# Shematic2.net
KiCad netlist of a schematic drawn in EAGLE
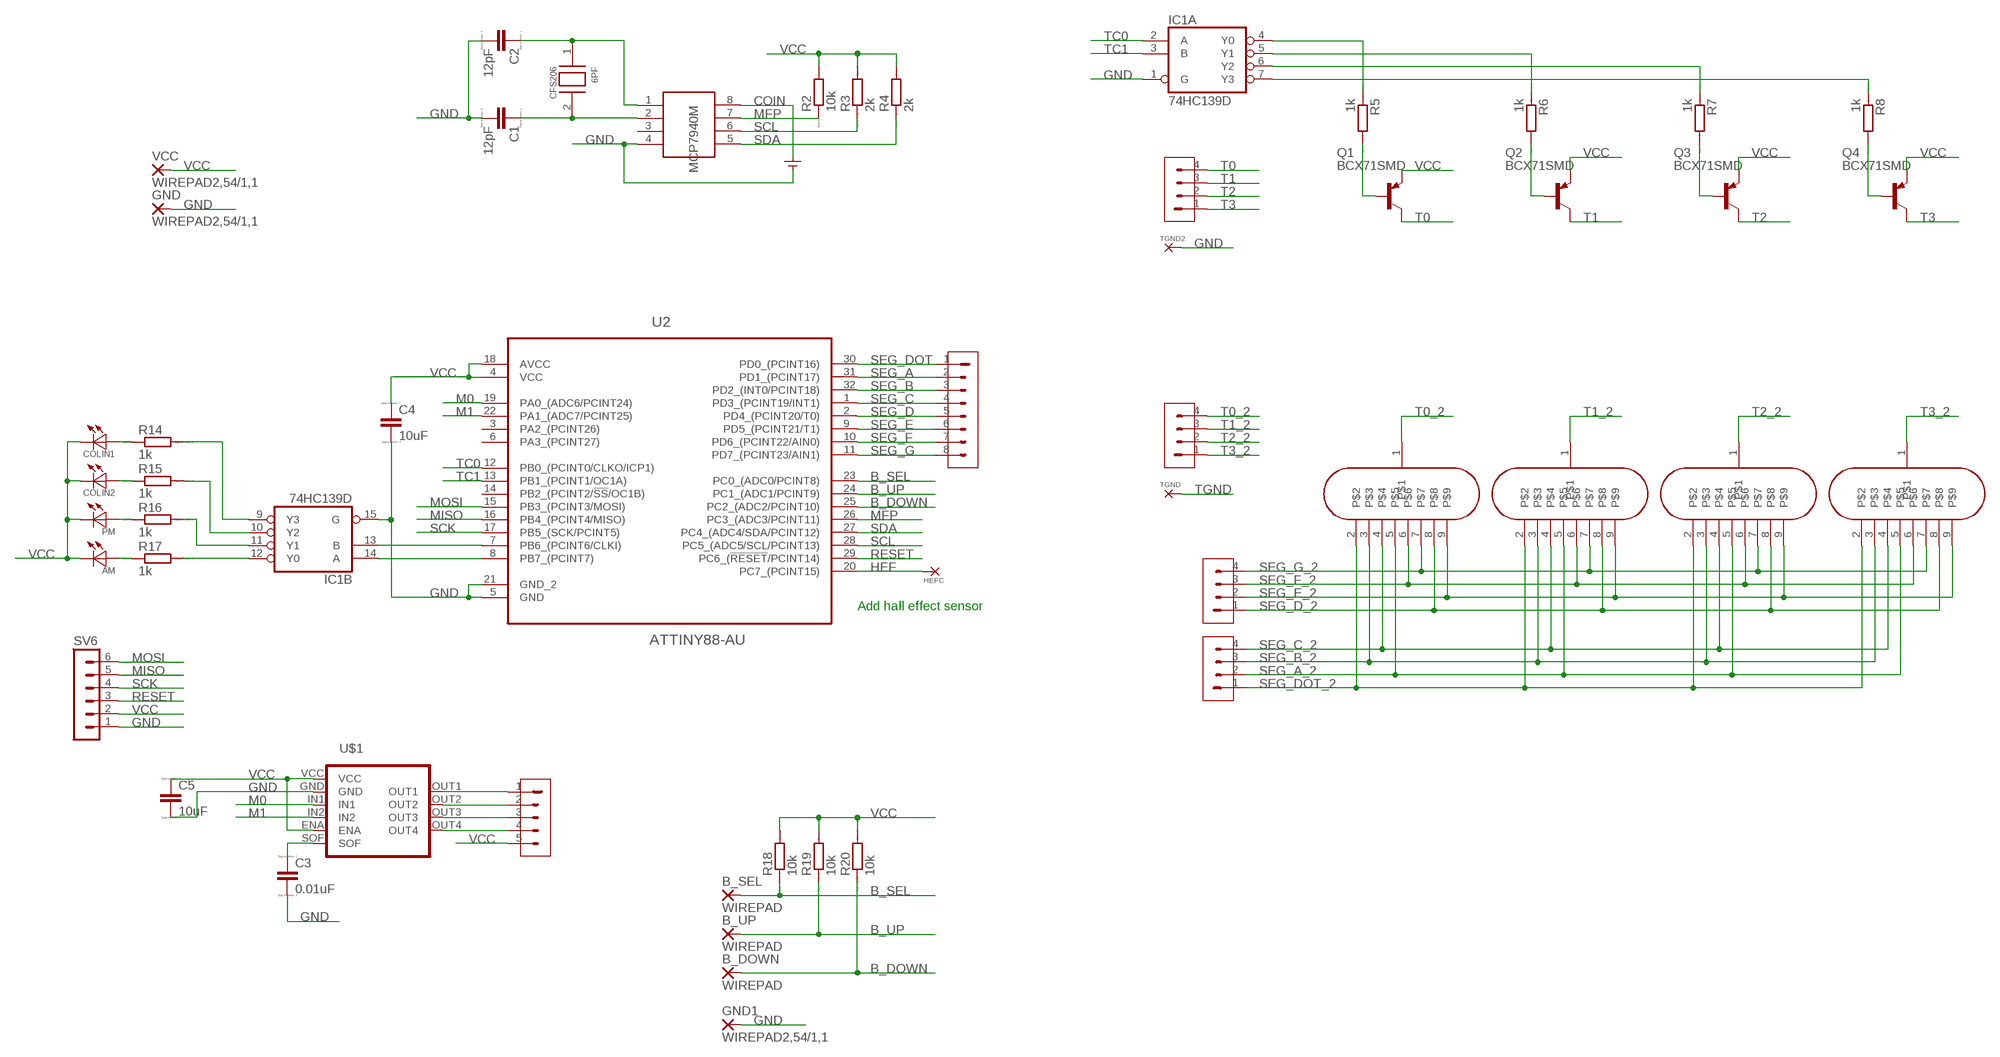
[diagram p0: schematic, sheet 1]

(export (version "E")
  (design (tool "Eeschema 10.0.6"))
  (components
    (comp (ref "6PF")
      (value "CFS206")
      (footprint "eagle-import:CFS206")
      (libsource (lib "eagle-import") (part "CFS206"))
    )
    (comp (ref "AM")
      (value "LED")
      (footprint "eagle-import:LED")
      (libsource (lib "eagle-import") (part "LED"))
    )
    (comp (ref "B_DOWN")
      (value "WIREPAD")
      (footprint "eagle-import:2,54_1,1")
      (libsource (lib "eagle-import") (part "WIREPAD2,54/1,1"))
    )
    (comp (ref "B_SEL")
      (value "WIREPAD")
      (footprint "eagle-import:2,54_1,1")
      (libsource (lib "eagle-import") (part "WIREPAD2,54/1,1"))
    )
    (comp (ref "B_UP")
      (value "WIREPAD")
      (footprint "eagle-import:2,54_1,1")
      (libsource (lib "eagle-import") (part "WIREPAD2,54/1,1"))
    )
    (comp (ref "C1")
      (value "12pF")
      (footprint "eagle-import:C1206")
      (libsource (lib "eagle-import") (part "CC1206"))
    )
    (comp (ref "C2")
      (value "12pF")
      (footprint "eagle-import:C1206")
      (libsource (lib "eagle-import") (part "CC1206"))
    )
    (comp (ref "C3")
      (value "0.01uF")
      (footprint "eagle-import:C1206")
      (libsource (lib "eagle-import") (part "CC1206"))
    )
    (comp (ref "C4")
      (value "10uF")
      (footprint "eagle-import:C1206")
      (libsource (lib "eagle-import") (part "CC1206"))
    )
    (comp (ref "C5")
      (value "10uF")
      (footprint "eagle-import:C1206")
      (libsource (lib "eagle-import") (part "CC1206"))
    )
    (comp (ref "COLIN1")
      (value "LED")
      (footprint "eagle-import:LED")
      (libsource (lib "eagle-import") (part "LED"))
    )
    (comp (ref "COLIN2")
      (value "LED")
      (footprint "eagle-import:LED")
      (libsource (lib "eagle-import") (part "LED"))
    )
    (comp (ref "GND")
      (value "WIREPAD2,54/1,1")
      (footprint "eagle-import:2,54_1,1")
      (libsource (lib "eagle-import") (part "WIREPAD2,54/1,1"))
    )
    (comp (ref "GND1")
      (value "WIREPAD2,54/1,1")
      (footprint "eagle-import:2,54_1,1")
      (libsource (lib "eagle-import") (part "WIREPAD2,54/1,1"))
    )
    (comp (ref "HEFC")
      (value "H01")
      (footprint "eagle-import:H01")
      (libsource (lib "eagle-import") (part "H01"))
    )
    (comp (ref "IC1")
      (value "74HC139D")
      (footprint "eagle-import:SO16")
      (libsource (lib "eagle-import") (part "74139DHC"))
    )
    (comp (ref "MCP7940M")
      (value "SOIC-8")
      (footprint "eagle-import:SOIC-8")
      (libsource (lib "eagle-import") (part "SOIC-8"))
    )
    (comp (ref "PM")
      (value "LED")
      (footprint "eagle-import:LED")
      (libsource (lib "eagle-import") (part "LED"))
    )
    (comp (ref "Q1")
      (value "BCX71SMD")
      (footprint "eagle-import:SOT23")
      (libsource (lib "eagle-import") (part "BCX71SMD"))
    )
    (comp (ref "Q2")
      (value "BCX71SMD")
      (footprint "eagle-import:SOT23")
      (libsource (lib "eagle-import") (part "BCX71SMD"))
    )
    (comp (ref "Q3")
      (value "BCX71SMD")
      (footprint "eagle-import:SOT23")
      (libsource (lib "eagle-import") (part "BCX71SMD"))
    )
    (comp (ref "Q4")
      (value "BCX71SMD")
      (footprint "eagle-import:SOT23")
      (libsource (lib "eagle-import") (part "BCX71SMD"))
    )
    (comp (ref "R2")
      (value "10k")
      (footprint "eagle-import:R1206")
      (libsource (lib "eagle-import") (part "RR1206"))
    )
    (comp (ref "R3")
      (value "2k")
      (footprint "eagle-import:R1206")
      (libsource (lib "eagle-import") (part "RR1206"))
    )
    (comp (ref "R4")
      (value "2k")
      (footprint "eagle-import:R1206")
      (libsource (lib "eagle-import") (part "RR1206"))
    )
    (comp (ref "R5")
      (value "1k")
      (footprint "eagle-import:R1206")
      (libsource (lib "eagle-import") (part "RR1206"))
    )
    (comp (ref "R6")
      (value "1k")
      (footprint "eagle-import:R1206")
      (libsource (lib "eagle-import") (part "RR1206"))
    )
    (comp (ref "R7")
      (value "1k")
      (footprint "eagle-import:R1206")
      (libsource (lib "eagle-import") (part "RR1206"))
    )
    (comp (ref "R8")
      (value "1k")
      (footprint "eagle-import:R1206")
      (libsource (lib "eagle-import") (part "RR1206"))
    )
    (comp (ref "R14")
      (value "1k")
      (footprint "eagle-import:R1206")
      (libsource (lib "eagle-import") (part "RR1206"))
    )
    (comp (ref "R15")
      (value "1k")
      (footprint "eagle-import:R1206")
      (libsource (lib "eagle-import") (part "RR1206"))
    )
    (comp (ref "R16")
      (value "1k")
      (footprint "eagle-import:R1206")
      (libsource (lib "eagle-import") (part "RR1206"))
    )
    (comp (ref "R17")
      (value "1k")
      (footprint "eagle-import:R1206")
      (libsource (lib "eagle-import") (part "RR1206"))
    )
    (comp (ref "R18")
      (value "10k")
      (footprint "eagle-import:R1206")
      (libsource (lib "eagle-import") (part "RR1206"))
    )
    (comp (ref "R19")
      (value "10k")
      (footprint "eagle-import:R1206")
      (libsource (lib "eagle-import") (part "RR1206"))
    )
    (comp (ref "R20")
      (value "10k")
      (footprint "eagle-import:R1206")
      (libsource (lib "eagle-import") (part "RR1206"))
    )
    (comp (ref "SV1")
      (value "H08")
      (footprint "eagle-import:H08")
      (libsource (lib "eagle-import") (part "H08"))
    )
    (comp (ref "SV2")
      (value "H04")
      (footprint "eagle-import:H04")
      (libsource (lib "eagle-import") (part "H04"))
    )
    (comp (ref "SV3")
      (value "H04")
      (footprint "eagle-import:H04")
      (libsource (lib "eagle-import") (part "H04"))
    )
    (comp (ref "SV4")
      (value "H05")
      (footprint "eagle-import:H05")
      (libsource (lib "eagle-import") (part "H05"))
    )
    (comp (ref "SV5")
      (value "H04")
      (footprint "eagle-import:H04")
      (libsource (lib "eagle-import") (part "H04"))
    )
    (comp (ref "SV6")
      (value "MA06-1")
      (footprint "eagle-import:MA06-1")
      (libsource (lib "eagle-import") (part "MA06-1"))
    )
    (comp (ref "SV7")
      (value "H04")
      (footprint "eagle-import:H04")
      (libsource (lib "eagle-import") (part "H04"))
    )
    (comp (ref "TGND")
      (value "H01")
      (footprint "eagle-import:H01")
      (libsource (lib "eagle-import") (part "H01"))
    )
    (comp (ref "TGND2")
      (value "H01")
      (footprint "eagle-import:H01")
      (libsource (lib "eagle-import") (part "H01"))
    )
    (comp (ref "TUBE0")
      (value "IV-9")
      (footprint "eagle-import:IV-9")
      (libsource (lib "eagle-import") (part "IV-9"))
    )
    (comp (ref "TUBE1")
      (value "IV-9")
      (footprint "eagle-import:IV-9")
      (libsource (lib "eagle-import") (part "IV-9"))
    )
    (comp (ref "TUBE2")
      (value "IV-9")
      (footprint "eagle-import:IV-9")
      (libsource (lib "eagle-import") (part "IV-9"))
    )
    (comp (ref "TUBE3")
      (value "IV-9")
      (footprint "eagle-import:IV-9")
      (libsource (lib "eagle-import") (part "IV-9"))
    )
    (comp (ref "U$1")
      (value "LB1848MC")
      (footprint "eagle-import:LB1848MC")
      (libsource (lib "eagle-import") (part "LB1848MC"))
    )
    (comp (ref "U$5")
      (value "COIN")
      (footprint "eagle-import:COIN")
      (libsource (lib "eagle-import") (part "COIN"))
    )
    (comp (ref "U2")
      (value "ATTINY88-AU")
      (footprint "eagle-import:QFP80P900X900X120-32N")
      (libsource (lib "eagle-import") (part "ATTINY88-AU"))
    )
    (comp (ref "VCC")
      (value "WIREPAD2,54/1,1")
      (footprint "eagle-import:2,54_1,1")
      (libsource (lib "eagle-import") (part "WIREPAD2,54/1,1"))
    )
  )
  (nets
    (net (code "1") (name "/B_DOWN") (class "Default")
      (node (ref "B_DOWN") (pin "1") (pinfunction "P_1") (pintype "passive"))
      (node (ref "R20") (pin "1") (pinfunction "1_1") (pintype "passive"))
      (node (ref "U2") (pin "25") (pinfunction "PC2_(ADC2/PCINT10)_25") (pintype "bidirectional"))
    )
    (net (code "2") (name "/B_SEL") (class "Default")
      (node (ref "B_SEL") (pin "1") (pinfunction "P_1") (pintype "passive"))
      (node (ref "R18") (pin "1") (pinfunction "1_1") (pintype "passive"))
      (node (ref "U2") (pin "23") (pinfunction "PC0_(ADC0/PCINT8)_23") (pintype "bidirectional"))
    )
    (net (code "3") (name "/B_UP") (class "Default")
      (node (ref "B_UP") (pin "1") (pinfunction "P_1") (pintype "passive"))
      (node (ref "R19") (pin "1") (pinfunction "1_1") (pintype "passive"))
      (node (ref "U2") (pin "24") (pinfunction "PC1_(ADC1/PCINT9)_24") (pintype "bidirectional"))
    )
    (net (code "4") (name "/COIN") (class "Default")
      (node (ref "MCP7940M") (pin "8") (pinfunction "P$8_8") (pintype "bidirectional"))
      (node (ref "U$5") (pin "V+") (pinfunction "V+_V+") (pintype "bidirectional"))
    )
    (net (code "5") (name "/GND") (class "Default")
      (node (ref "C1") (pin "2") (pinfunction "2_2") (pintype "passive"))
      (node (ref "C2") (pin "2") (pinfunction "2_2") (pintype "passive"))
      (node (ref "C3") (pin "2") (pinfunction "2_2") (pintype "passive"))
      (node (ref "C4") (pin "2") (pinfunction "2_2") (pintype "passive"))
      (node (ref "C5") (pin "2") (pinfunction "2_2") (pintype "passive"))
      (node (ref "GND") (pin "1") (pinfunction "P_1") (pintype "passive"))
      (node (ref "GND1") (pin "1") (pinfunction "P_1") (pintype "passive"))
      (node (ref "IC1") (pin "1") (pinfunction "G_1") (pintype "input"))
      (node (ref "IC1") (pin "15") (pinfunction "G_15") (pintype "input"))
      (node (ref "MCP7940M") (pin "4") (pinfunction "P$4_4") (pintype "bidirectional"))
      (node (ref "SV6") (pin "1") (pinfunction "1_1") (pintype "passive"))
      (node (ref "TGND2") (pin "P$1") (pinfunction "P$1_P$1") (pintype "bidirectional"))
      (node (ref "U$1") (pin "GND") (pinfunction "GND_GND") (pintype "bidirectional"))
      (node (ref "U$5") (pin "V-") (pinfunction "V-_V-") (pintype "bidirectional"))
      (node (ref "U2") (pin "21") (pinfunction "GND_2_21") (pintype "passive"))
      (node (ref "U2") (pin "5") (pinfunction "GND_5") (pintype "passive"))
    )
    (net (code "6") (name "/HEF") (class "Default")
      (node (ref "HEFC") (pin "P$1") (pinfunction "P$1_P$1") (pintype "bidirectional"))
      (node (ref "U2") (pin "20") (pinfunction "PC7_(PCINT15)_20") (pintype "bidirectional"))
    )
    (net (code "7") (name "/M0") (class "Default")
      (node (ref "U$1") (pin "IN1") (pinfunction "IN1_IN1") (pintype "bidirectional"))
      (node (ref "U2") (pin "19") (pinfunction "PA0_(ADC6/PCINT24)_19") (pintype "bidirectional"))
    )
    (net (code "8") (name "/M1") (class "Default")
      (node (ref "U$1") (pin "IN2") (pinfunction "IN2_IN2") (pintype "bidirectional"))
      (node (ref "U2") (pin "22") (pinfunction "PA1_(ADC7/PCINT25)_22") (pintype "bidirectional"))
    )
    (net (code "9") (name "/MFP") (class "Default")
      (node (ref "MCP7940M") (pin "7") (pinfunction "P$7_7") (pintype "bidirectional"))
      (node (ref "R2") (pin "1") (pinfunction "1_1") (pintype "passive"))
      (node (ref "U2") (pin "26") (pinfunction "PC3_(ADC3/PCINT11)_26") (pintype "bidirectional"))
    )
    (net (code "10") (name "/MISO") (class "Default")
      (node (ref "SV6") (pin "5") (pinfunction "5_5") (pintype "passive"))
      (node (ref "U2") (pin "16") (pinfunction "PB4_(PCINT4/MISO)_16") (pintype "bidirectional"))
    )
    (net (code "11") (name "/MOSI") (class "Default")
      (node (ref "SV6") (pin "6") (pinfunction "6_6") (pintype "passive"))
      (node (ref "U2") (pin "15") (pinfunction "PB3_(PCINT3/MOSI)_15") (pintype "bidirectional"))
    )
    (net (code "12") (name "/RESET") (class "Default")
      (node (ref "SV6") (pin "3") (pinfunction "3_3") (pintype "passive"))
      (node (ref "U2") (pin "29") (pinfunction "PC6_(~{RESET}/PCINT14)_29") (pintype "bidirectional"))
    )
    (net (code "13") (name "/SCK") (class "Default")
      (node (ref "SV6") (pin "4") (pinfunction "4_4") (pintype "passive"))
      (node (ref "U2") (pin "17") (pinfunction "PB5_(SCK/PCINT5)_17") (pintype "bidirectional"))
    )
    (net (code "14") (name "/SCL") (class "Default")
      (node (ref "MCP7940M") (pin "6") (pinfunction "P$6_6") (pintype "bidirectional"))
      (node (ref "R3") (pin "1") (pinfunction "1_1") (pintype "passive"))
      (node (ref "U2") (pin "28") (pinfunction "PC5_(ADC5/SCL/PCINT13)_28") (pintype "bidirectional"))
    )
    (net (code "15") (name "/SDA") (class "Default")
      (node (ref "MCP7940M") (pin "5") (pinfunction "P$5_5") (pintype "bidirectional"))
      (node (ref "R4") (pin "1") (pinfunction "1_1") (pintype "passive"))
      (node (ref "U2") (pin "27") (pinfunction "PC4_(ADC4/SDA/PCINT12)_27") (pintype "bidirectional"))
    )
    (net (code "16") (name "/SEG_A") (class "Default")
      (node (ref "SV1") (pin "2") (pinfunction "2_2") (pintype "bidirectional"))
      (node (ref "U2") (pin "31") (pinfunction "PD1_(PCINT17)_31") (pintype "bidirectional"))
    )
    (net (code "17") (name "/SEG_A_2") (class "Default")
      (node (ref "SV7") (pin "2") (pinfunction "2_2") (pintype "bidirectional"))
      (node (ref "TUBE0") (pin "5") (pinfunction "P$5_5") (pintype "bidirectional"))
      (node (ref "TUBE1") (pin "5") (pinfunction "P$5_5") (pintype "bidirectional"))
      (node (ref "TUBE2") (pin "5") (pinfunction "P$5_5") (pintype "bidirectional"))
      (node (ref "TUBE3") (pin "5") (pinfunction "P$5_5") (pintype "bidirectional"))
    )
    (net (code "18") (name "/SEG_B") (class "Default")
      (node (ref "SV1") (pin "3") (pinfunction "3_3") (pintype "bidirectional"))
      (node (ref "U2") (pin "32") (pinfunction "PD2_(INT0/PCINT18)_32") (pintype "bidirectional"))
    )
    (net (code "19") (name "/SEG_B_2") (class "Default")
      (node (ref "SV7") (pin "3") (pinfunction "3_3") (pintype "bidirectional"))
      (node (ref "TUBE0") (pin "3") (pinfunction "P$3_3") (pintype "bidirectional"))
      (node (ref "TUBE1") (pin "3") (pinfunction "P$3_3") (pintype "bidirectional"))
      (node (ref "TUBE2") (pin "3") (pinfunction "P$3_3") (pintype "bidirectional"))
      (node (ref "TUBE3") (pin "3") (pinfunction "P$3_3") (pintype "bidirectional"))
    )
    (net (code "20") (name "/SEG_C") (class "Default")
      (node (ref "SV1") (pin "4") (pinfunction "4_4") (pintype "bidirectional"))
      (node (ref "U2") (pin "1") (pinfunction "PD3_(PCINT19/INT1)_1") (pintype "bidirectional"))
    )
    (net (code "21") (name "/SEG_C_2") (class "Default")
      (node (ref "SV7") (pin "4") (pinfunction "4_4") (pintype "bidirectional"))
      (node (ref "TUBE0") (pin "4") (pinfunction "P$4_4") (pintype "bidirectional"))
      (node (ref "TUBE1") (pin "4") (pinfunction "P$4_4") (pintype "bidirectional"))
      (node (ref "TUBE2") (pin "4") (pinfunction "P$4_4") (pintype "bidirectional"))
      (node (ref "TUBE3") (pin "4") (pinfunction "P$4_4") (pintype "bidirectional"))
    )
    (net (code "22") (name "/SEG_D") (class "Default")
      (node (ref "SV1") (pin "5") (pinfunction "5_5") (pintype "bidirectional"))
      (node (ref "U2") (pin "2") (pinfunction "PD4_(PCINT20/T0)_2") (pintype "bidirectional"))
    )
    (net (code "23") (name "/SEG_DOT") (class "Default")
      (node (ref "SV1") (pin "1") (pinfunction "1_1") (pintype "bidirectional"))
      (node (ref "U2") (pin "30") (pinfunction "PD0_(PCINT16)_30") (pintype "bidirectional"))
    )
    (net (code "24") (name "/SEG_DOT_2") (class "Default")
      (node (ref "SV7") (pin "1") (pinfunction "1_1") (pintype "bidirectional"))
      (node (ref "TUBE0") (pin "2") (pinfunction "P$2_2") (pintype "bidirectional"))
      (node (ref "TUBE1") (pin "2") (pinfunction "P$2_2") (pintype "bidirectional"))
      (node (ref "TUBE2") (pin "2") (pinfunction "P$2_2") (pintype "bidirectional"))
      (node (ref "TUBE3") (pin "2") (pinfunction "P$2_2") (pintype "bidirectional"))
    )
    (net (code "25") (name "/SEG_D_2") (class "Default")
      (node (ref "SV2") (pin "1") (pinfunction "1_1") (pintype "bidirectional"))
      (node (ref "TUBE0") (pin "8") (pinfunction "P$8_8") (pintype "bidirectional"))
      (node (ref "TUBE1") (pin "8") (pinfunction "P$8_8") (pintype "bidirectional"))
      (node (ref "TUBE2") (pin "8") (pinfunction "P$8_8") (pintype "bidirectional"))
      (node (ref "TUBE3") (pin "8") (pinfunction "P$8_8") (pintype "bidirectional"))
    )
    (net (code "26") (name "/SEG_E") (class "Default")
      (node (ref "SV1") (pin "6") (pinfunction "6_6") (pintype "bidirectional"))
      (node (ref "U2") (pin "9") (pinfunction "PD5_(PCINT21/T1)_9") (pintype "bidirectional"))
    )
    (net (code "27") (name "/SEG_E_2") (class "Default")
      (node (ref "SV2") (pin "2") (pinfunction "2_2") (pintype "bidirectional"))
      (node (ref "TUBE0") (pin "9") (pinfunction "P$9_9") (pintype "bidirectional"))
      (node (ref "TUBE1") (pin "9") (pinfunction "P$9_9") (pintype "bidirectional"))
      (node (ref "TUBE2") (pin "9") (pinfunction "P$9_9") (pintype "bidirectional"))
      (node (ref "TUBE3") (pin "9") (pinfunction "P$9_9") (pintype "bidirectional"))
    )
    (net (code "28") (name "/SEG_F") (class "Default")
      (node (ref "SV1") (pin "7") (pinfunction "7_7") (pintype "bidirectional"))
      (node (ref "U2") (pin "10") (pinfunction "PD6_(PCINT22/AIN0)_10") (pintype "bidirectional"))
    )
    (net (code "29") (name "/SEG_F_2") (class "Default")
      (node (ref "SV2") (pin "3") (pinfunction "3_3") (pintype "bidirectional"))
      (node (ref "TUBE0") (pin "6") (pinfunction "P$6_6") (pintype "bidirectional"))
      (node (ref "TUBE1") (pin "6") (pinfunction "P$6_6") (pintype "bidirectional"))
      (node (ref "TUBE2") (pin "6") (pinfunction "P$6_6") (pintype "bidirectional"))
      (node (ref "TUBE3") (pin "6") (pinfunction "P$6_6") (pintype "bidirectional"))
    )
    (net (code "30") (name "/SEG_G") (class "Default")
      (node (ref "SV1") (pin "8") (pinfunction "8_8") (pintype "bidirectional"))
      (node (ref "U2") (pin "11") (pinfunction "PD7_(PCINT23/AIN1)_11") (pintype "bidirectional"))
    )
    (net (code "31") (name "/SEG_G_2") (class "Default")
      (node (ref "SV2") (pin "4") (pinfunction "4_4") (pintype "bidirectional"))
      (node (ref "TUBE0") (pin "7") (pinfunction "P$7_7") (pintype "bidirectional"))
      (node (ref "TUBE1") (pin "7") (pinfunction "P$7_7") (pintype "bidirectional"))
      (node (ref "TUBE2") (pin "7") (pinfunction "P$7_7") (pintype "bidirectional"))
      (node (ref "TUBE3") (pin "7") (pinfunction "P$7_7") (pintype "bidirectional"))
    )
    (net (code "32") (name "/T0") (class "Default")
      (node (ref "Q1") (pin "3") (pinfunction "C_3") (pintype "passive"))
      (node (ref "SV5") (pin "4") (pinfunction "4_4") (pintype "bidirectional"))
    )
    (net (code "33") (name "/T0_2") (class "Default")
      (node (ref "SV3") (pin "4") (pinfunction "4_4") (pintype "bidirectional"))
      (node (ref "TUBE0") (pin "1") (pinfunction "P$1_1") (pintype "bidirectional"))
    )
    (net (code "34") (name "/T1") (class "Default")
      (node (ref "Q2") (pin "3") (pinfunction "C_3") (pintype "passive"))
      (node (ref "SV5") (pin "3") (pinfunction "3_3") (pintype "bidirectional"))
    )
    (net (code "35") (name "/T1_2") (class "Default")
      (node (ref "SV3") (pin "3") (pinfunction "3_3") (pintype "bidirectional"))
      (node (ref "TUBE1") (pin "1") (pinfunction "P$1_1") (pintype "bidirectional"))
    )
    (net (code "36") (name "/T2") (class "Default")
      (node (ref "Q3") (pin "3") (pinfunction "C_3") (pintype "passive"))
      (node (ref "SV5") (pin "2") (pinfunction "2_2") (pintype "bidirectional"))
    )
    (net (code "37") (name "/T2_2") (class "Default")
      (node (ref "SV3") (pin "2") (pinfunction "2_2") (pintype "bidirectional"))
      (node (ref "TUBE2") (pin "1") (pinfunction "P$1_1") (pintype "bidirectional"))
    )
    (net (code "38") (name "/T3") (class "Default")
      (node (ref "Q4") (pin "3") (pinfunction "C_3") (pintype "passive"))
      (node (ref "SV5") (pin "1") (pinfunction "1_1") (pintype "bidirectional"))
    )
    (net (code "39") (name "/T3_2") (class "Default")
      (node (ref "SV3") (pin "1") (pinfunction "1_1") (pintype "bidirectional"))
      (node (ref "TUBE3") (pin "1") (pinfunction "P$1_1") (pintype "bidirectional"))
    )
    (net (code "40") (name "/TC0") (class "Default")
      (node (ref "IC1") (pin "2") (pinfunction "A_2") (pintype "input"))
      (node (ref "U2") (pin "12") (pinfunction "PB0_(PCINT0/CLKO/ICP1)_12") (pintype "bidirectional"))
    )
    (net (code "41") (name "/TC1") (class "Default")
      (node (ref "IC1") (pin "3") (pinfunction "B_3") (pintype "input"))
      (node (ref "U2") (pin "13") (pinfunction "PB1_(PCINT1/OC1A)_13") (pintype "bidirectional"))
    )
    (net (code "42") (name "/TGND") (class "Default")
      (node (ref "TGND") (pin "P$1") (pinfunction "P$1_P$1") (pintype "bidirectional"))
    )
    (net (code "43") (name "/VCC") (class "Default")
      (node (ref "AM") (pin "P$2") (pinfunction "P$2_P$2") (pintype "bidirectional"))
      (node (ref "C4") (pin "1") (pinfunction "1_1") (pintype "passive"))
      (node (ref "C5") (pin "1") (pinfunction "1_1") (pintype "passive"))
      (node (ref "COLIN1") (pin "P$2") (pinfunction "P$2_P$2") (pintype "bidirectional"))
      (node (ref "COLIN2") (pin "P$2") (pinfunction "P$2_P$2") (pintype "bidirectional"))
      (node (ref "PM") (pin "P$2") (pinfunction "P$2_P$2") (pintype "bidirectional"))
      (node (ref "Q1") (pin "2") (pinfunction "E_2") (pintype "passive"))
      (node (ref "Q2") (pin "2") (pinfunction "E_2") (pintype "passive"))
      (node (ref "Q3") (pin "2") (pinfunction "E_2") (pintype "passive"))
      (node (ref "Q4") (pin "2") (pinfunction "E_2") (pintype "passive"))
      (node (ref "R18") (pin "2") (pinfunction "2_2") (pintype "passive"))
      (node (ref "R19") (pin "2") (pinfunction "2_2") (pintype "passive"))
      (node (ref "R2") (pin "2") (pinfunction "2_2") (pintype "passive"))
      (node (ref "R20") (pin "2") (pinfunction "2_2") (pintype "passive"))
      (node (ref "R3") (pin "2") (pinfunction "2_2") (pintype "passive"))
      (node (ref "R4") (pin "2") (pinfunction "2_2") (pintype "passive"))
      (node (ref "SV4") (pin "5") (pinfunction "5_5") (pintype "bidirectional"))
      (node (ref "SV6") (pin "2") (pinfunction "2_2") (pintype "passive"))
      (node (ref "U$1") (pin "ENA") (pinfunction "ENA_ENA") (pintype "bidirectional"))
      (node (ref "U$1") (pin "VCC") (pinfunction "VCC_VCC") (pintype "bidirectional"))
      (node (ref "U2") (pin "18") (pinfunction "AVCC_18") (pintype "power_in"))
      (node (ref "U2") (pin "4") (pinfunction "VCC_4") (pintype "power_in"))
      (node (ref "VCC") (pin "1") (pinfunction "P_1") (pintype "passive"))
    )
    (net (code "44") (name "Net-(6PF-P$1)") (class "Default")
      (node (ref "6PF") (pin "1") (pinfunction "P$1_1") (pintype "bidirectional"))
      (node (ref "C2") (pin "1") (pinfunction "1_1") (pintype "passive"))
      (node (ref "MCP7940M") (pin "1") (pinfunction "P$1_1") (pintype "bidirectional"))
    )
    (net (code "45") (name "Net-(6PF-P$2)") (class "Default")
      (node (ref "6PF") (pin "2") (pinfunction "P$2_2") (pintype "bidirectional"))
      (node (ref "C1") (pin "1") (pinfunction "1_1") (pintype "passive"))
      (node (ref "MCP7940M") (pin "2") (pinfunction "P$2_2") (pintype "bidirectional"))
    )
    (net (code "46") (name "Net-(AM-PadP$1)") (class "Default")
      (node (ref "AM") (pin "P$1") (pinfunction "P$1_P$1") (pintype "bidirectional"))
      (node (ref "R17") (pin "1") (pinfunction "1_1") (pintype "passive"))
    )
    (net (code "47") (name "Net-(C3-Pad1)") (class "Default")
      (node (ref "C3") (pin "1") (pinfunction "1_1") (pintype "passive"))
      (node (ref "U$1") (pin "SOF") (pinfunction "SOF_SOF") (pintype "bidirectional"))
    )
    (net (code "48") (name "Net-(COLIN1-PadP$1)") (class "Default")
      (node (ref "COLIN1") (pin "P$1") (pinfunction "P$1_P$1") (pintype "bidirectional"))
      (node (ref "R14") (pin "1") (pinfunction "1_1") (pintype "passive"))
    )
    (net (code "49") (name "Net-(COLIN2-PadP$1)") (class "Default")
      (node (ref "COLIN2") (pin "P$1") (pinfunction "P$1_P$1") (pintype "bidirectional"))
      (node (ref "R15") (pin "1") (pinfunction "1_1") (pintype "passive"))
    )
    (net (code "50") (name "Net-(IC1A-Y0)") (class "Default")
      (node (ref "IC1") (pin "4") (pinfunction "Y0_4") (pintype "output"))
      (node (ref "R5") (pin "1") (pinfunction "1_1") (pintype "passive"))
    )
    (net (code "51") (name "Net-(IC1A-Y1)") (class "Default")
      (node (ref "IC1") (pin "5") (pinfunction "Y1_5") (pintype "output"))
      (node (ref "R6") (pin "1") (pinfunction "1_1") (pintype "passive"))
    )
    (net (code "52") (name "Net-(IC1A-Y2)") (class "Default")
      (node (ref "IC1") (pin "6") (pinfunction "Y2_6") (pintype "output"))
      (node (ref "R7") (pin "1") (pinfunction "1_1") (pintype "passive"))
    )
    (net (code "53") (name "Net-(IC1A-Y3)") (class "Default")
      (node (ref "IC1") (pin "7") (pinfunction "Y3_7") (pintype "output"))
      (node (ref "R8") (pin "1") (pinfunction "1_1") (pintype "passive"))
    )
    (net (code "54") (name "Net-(IC1B-A)") (class "Default")
      (node (ref "IC1") (pin "14") (pinfunction "A_14") (pintype "input"))
      (node (ref "U2") (pin "8") (pinfunction "PB7_(PCINT7)_8") (pintype "bidirectional"))
    )
    (net (code "55") (name "Net-(IC1B-B)") (class "Default")
      (node (ref "IC1") (pin "13") (pinfunction "B_13") (pintype "input"))
      (node (ref "U2") (pin "7") (pinfunction "PB6_(PCINT6/CLKI)_7") (pintype "bidirectional"))
    )
    (net (code "56") (name "Net-(IC1B-Y0)") (class "Default")
      (node (ref "IC1") (pin "12") (pinfunction "Y0_12") (pintype "output"))
      (node (ref "R17") (pin "2") (pinfunction "2_2") (pintype "passive"))
    )
    (net (code "57") (name "Net-(IC1B-Y1)") (class "Default")
      (node (ref "IC1") (pin "11") (pinfunction "Y1_11") (pintype "output"))
      (node (ref "R16") (pin "2") (pinfunction "2_2") (pintype "passive"))
    )
    (net (code "58") (name "Net-(IC1B-Y2)") (class "Default")
      (node (ref "IC1") (pin "10") (pinfunction "Y2_10") (pintype "output"))
      (node (ref "R15") (pin "2") (pinfunction "2_2") (pintype "passive"))
    )
    (net (code "59") (name "Net-(IC1B-Y3)") (class "Default")
      (node (ref "IC1") (pin "9") (pinfunction "Y3_9") (pintype "output"))
      (node (ref "R14") (pin "2") (pinfunction "2_2") (pintype "passive"))
    )
    (net (code "60") (name "Net-(PM-PadP$1)") (class "Default")
      (node (ref "PM") (pin "P$1") (pinfunction "P$1_P$1") (pintype "bidirectional"))
      (node (ref "R16") (pin "1") (pinfunction "1_1") (pintype "passive"))
    )
    (net (code "61") (name "Net-(Q1-B)") (class "Default")
      (node (ref "Q1") (pin "1") (pinfunction "B_1") (pintype "passive"))
      (node (ref "R5") (pin "2") (pinfunction "2_2") (pintype "passive"))
    )
    (net (code "62") (name "Net-(Q2-B)") (class "Default")
      (node (ref "Q2") (pin "1") (pinfunction "B_1") (pintype "passive"))
      (node (ref "R6") (pin "2") (pinfunction "2_2") (pintype "passive"))
    )
    (net (code "63") (name "Net-(Q3-B)") (class "Default")
      (node (ref "Q3") (pin "1") (pinfunction "B_1") (pintype "passive"))
      (node (ref "R7") (pin "2") (pinfunction "2_2") (pintype "passive"))
    )
    (net (code "64") (name "Net-(Q4-B)") (class "Default")
      (node (ref "Q4") (pin "1") (pinfunction "B_1") (pintype "passive"))
      (node (ref "R8") (pin "2") (pinfunction "2_2") (pintype "passive"))
    )
    (net (code "65") (name "Net-(SV4-Pad1)") (class "Default")
      (node (ref "SV4") (pin "1") (pinfunction "1_1") (pintype "bidirectional"))
      (node (ref "U$1") (pin "OUT1") (pinfunction "OUT1_OUT1") (pintype "bidirectional"))
    )
    (net (code "66") (name "Net-(SV4-Pad2)") (class "Default")
      (node (ref "SV4") (pin "2") (pinfunction "2_2") (pintype "bidirectional"))
      (node (ref "U$1") (pin "OUT2") (pinfunction "OUT2_OUT2") (pintype "bidirectional"))
    )
    (net (code "67") (name "Net-(SV4-Pad3)") (class "Default")
      (node (ref "SV4") (pin "3") (pinfunction "3_3") (pintype "bidirectional"))
      (node (ref "U$1") (pin "OUT3") (pinfunction "OUT3_OUT3") (pintype "bidirectional"))
    )
    (net (code "68") (name "Net-(SV4-Pad4)") (class "Default")
      (node (ref "SV4") (pin "4") (pinfunction "4_4") (pintype "bidirectional"))
      (node (ref "U$1") (pin "OUT4") (pinfunction "OUT4_OUT4") (pintype "bidirectional"))
    )
    (net (code "69") (name "unconnected-(MCP7940M-P$3-Pad3)") (class "Default")
      (node (ref "MCP7940M") (pin "3") (pinfunction "P$3_3") (pintype "bidirectional"))
    )
    (net (code "70") (name "unconnected-(U2-PA2_(PCINT26)-Pad3)") (class "Default")
      (node (ref "U2") (pin "3") (pinfunction "PA2_(PCINT26)_3") (pintype "bidirectional"))
    )
    (net (code "71") (name "unconnected-(U2-PA3_(PCINT27)-Pad6)") (class "Default")
      (node (ref "U2") (pin "6") (pinfunction "PA3_(PCINT27)_6") (pintype "bidirectional"))
    )
    (net (code "72") (name "unconnected-(U2-PB2_(PCINT2{slash}~{SS}{slash}OC1B)-Pad14)") (class "Default")
      (node (ref "U2") (pin "14") (pinfunction "PB2_(PCINT2/~{SS}/OC1B)_14") (pintype "bidirectional"))
    )
  )
)
